# main.net
KiCad netlist of a schematic drawn in EAGLE
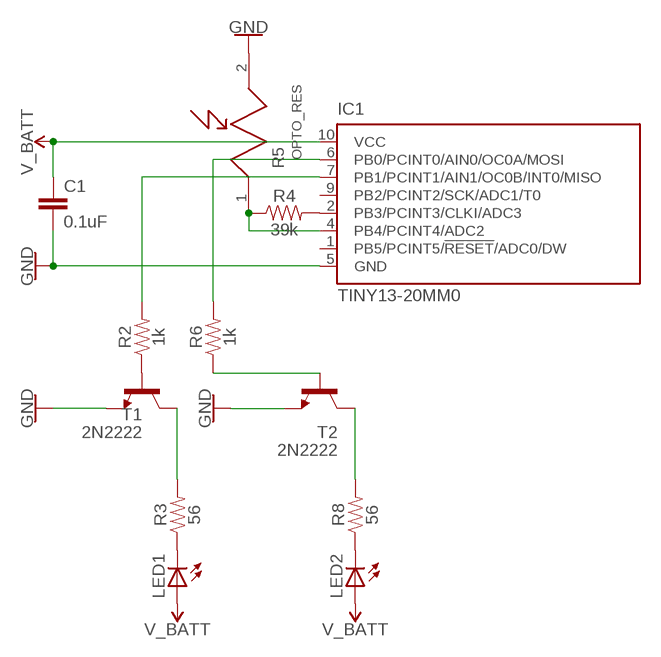
[diagram p0: schematic, sheet 1]

(export (version "E")
  (design (tool "Eeschema 10.0.6"))
  (components
    (comp (ref "C1")
      (value "0.1uF")
      (footprint "eagle-import:CAP-PTH-SMALL-KIT")
      (libsource (lib "eagle-import") (part "0.1UF-KIT-EZ-50V-20%"))
    )
    (comp (ref "IC1")
      (value "TINY13-20MM0")
      (footprint "eagle-import:10M1")
      (fields (field (name "MPN") "ATTINY13A-MMU"))
      (libsource (lib "eagle-import") (part "TINY13MM0-20"))
    )
    (comp (ref "LED1")
      (value "LEDTOPLED-SANTANA")
      (footprint "eagle-import:MINI-TOPLED-SANTANA")
      (libsource (lib "eagle-import") (part "LEDTOPLED-SANTANA"))
    )
    (comp (ref "LED2")
      (value "LEDTOPLED-SANTANA")
      (footprint "eagle-import:MINI-TOPLED-SANTANA")
      (libsource (lib "eagle-import") (part "LEDTOPLED-SANTANA"))
    )
    (comp (ref "R2")
      (value "1k")
      (footprint "eagle-import:0805")
      (libsource (lib "eagle-import") (part "RESISTOR0805"))
    )
    (comp (ref "R3")
      (value "56")
      (footprint "eagle-import:0805")
      (libsource (lib "eagle-import") (part "RESISTOR0805"))
    )
    (comp (ref "R4")
      (value "39k")
      (footprint "eagle-import:0805")
      (libsource (lib "eagle-import") (part "RESISTOR0805"))
    )
    (comp (ref "R5")
      (value "OPTO_RES")
      (footprint "eagle-import:OPTO_RES")
      (libsource (lib "eagle-import") (part "OPTO_RES"))
    )
    (comp (ref "R6")
      (value "1k")
      (footprint "eagle-import:0805")
      (libsource (lib "eagle-import") (part "RESISTOR0805"))
    )
    (comp (ref "R8")
      (value "56")
      (footprint "eagle-import:0805")
      (libsource (lib "eagle-import") (part "RESISTOR0805"))
    )
    (comp (ref "T1")
      (value "2N2222")
      (footprint "eagle-import:TO92-EBC-OVAL")
      (libsource (lib "eagle-import") (part "2N2222"))
    )
    (comp (ref "T2")
      (value "2N2222")
      (footprint "eagle-import:TO92-EBC-OVAL")
      (libsource (lib "eagle-import") (part "2N2222"))
    )
  )
  (nets
    (net (code "1") (name "GND") (class "Default")
      (node (ref "C1") (pin "2") (pinfunction "2_2") (pintype "passive"))
      (node (ref "IC1") (pin "5") (pinfunction "GND_5") (pintype "power_in"))
      (node (ref "R5") (pin "2") (pinfunction "P2_2") (pintype "bidirectional"))
      (node (ref "T1") (pin "E") (pinfunction "E_E") (pintype "passive"))
      (node (ref "T2") (pin "E") (pinfunction "E_E") (pintype "passive"))
    )
    (net (code "2") (name "Net-(IC1A-PB0{slash}PCINT0{slash}AIN0{slash}OC0A{slash}MOSI)") (class "Default")
      (node (ref "IC1") (pin "6") (pinfunction "PB0/PCINT0/AIN0/OC0A/MOSI_6") (pintype "bidirectional"))
      (node (ref "R6") (pin "2") (pinfunction "2_2") (pintype "passive"))
    )
    (net (code "3") (name "Net-(IC1A-PB1{slash}PCINT1{slash}AIN1{slash}OC0B{slash}INT0{slash}MISO)") (class "Default")
      (node (ref "IC1") (pin "7") (pinfunction "PB1/PCINT1/AIN1/OC0B/INT0/MISO_7") (pintype "bidirectional"))
      (node (ref "R2") (pin "2") (pinfunction "2_2") (pintype "passive"))
    )
    (net (code "4") (name "Net-(IC1A-PB3{slash}PCINT3{slash}CLKI{slash}ADC3)") (class "Default")
      (node (ref "IC1") (pin "2") (pinfunction "PB3/PCINT3/CLKI/ADC3_2") (pintype "bidirectional"))
      (node (ref "R4") (pin "2") (pinfunction "2_2") (pintype "passive"))
    )
    (net (code "5") (name "Net-(IC1A-PB4{slash}PCINT4{slash}ADC2)") (class "Default")
      (node (ref "IC1") (pin "4") (pinfunction "PB4/PCINT4/ADC2_4") (pintype "bidirectional"))
      (node (ref "R4") (pin "1") (pinfunction "1_1") (pintype "passive"))
      (node (ref "R5") (pin "1") (pinfunction "P1_1") (pintype "bidirectional"))
    )
    (net (code "6") (name "Net-(LED1-PadC)") (class "Default")
      (node (ref "LED1") (pin "C") (pinfunction "C_C") (pintype "passive"))
      (node (ref "R3") (pin "1") (pinfunction "1_1") (pintype "passive"))
    )
    (net (code "7") (name "Net-(LED2-PadC)") (class "Default")
      (node (ref "LED2") (pin "C") (pinfunction "C_C") (pintype "passive"))
      (node (ref "R8") (pin "1") (pinfunction "1_1") (pintype "passive"))
    )
    (net (code "8") (name "Net-(R2-Pad1)") (class "Default")
      (node (ref "R2") (pin "1") (pinfunction "1_1") (pintype "passive"))
      (node (ref "T1") (pin "B") (pinfunction "B_B") (pintype "passive"))
    )
    (net (code "9") (name "Net-(R3-Pad2)") (class "Default")
      (node (ref "R3") (pin "2") (pinfunction "2_2") (pintype "passive"))
      (node (ref "T1") (pin "C") (pinfunction "C_C") (pintype "passive"))
    )
    (net (code "10") (name "Net-(R6-Pad1)") (class "Default")
      (node (ref "R6") (pin "1") (pinfunction "1_1") (pintype "passive"))
      (node (ref "T2") (pin "B") (pinfunction "B_B") (pintype "passive"))
    )
    (net (code "11") (name "Net-(R8-Pad2)") (class "Default")
      (node (ref "R8") (pin "2") (pinfunction "2_2") (pintype "passive"))
      (node (ref "T2") (pin "C") (pinfunction "C_C") (pintype "passive"))
    )
    (net (code "12") (name "V_BATT") (class "Default")
      (node (ref "C1") (pin "1") (pinfunction "1_1") (pintype "passive"))
      (node (ref "IC1") (pin "10") (pinfunction "VCC_10") (pintype "power_in"))
      (node (ref "LED1") (pin "A") (pinfunction "A_A") (pintype "passive"))
      (node (ref "LED2") (pin "A") (pinfunction "A_A") (pintype "passive"))
    )
    (net (code "13") (name "unconnected-(IC1A-PB2{slash}PCINT2{slash}SCK{slash}ADC1{slash}T0-Pad9)") (class "Default")
      (node (ref "IC1") (pin "9") (pinfunction "PB2/PCINT2/SCK/ADC1/T0_9") (pintype "bidirectional"))
    )
    (net (code "14") (name "unconnected-(IC1A-PB5{slash}PCINT5{slash}~{RESET}{slash}ADC0{slash}DW-Pad1)") (class "Default")
      (node (ref "IC1") (pin "1") (pinfunction "PB5/PCINT5/~{RESET}/ADC0/DW_1") (pintype "bidirectional"))
    )
  )
)
